# TPS7A4701_and_3301.net
KiCad netlist of a schematic drawn in Altium Designer
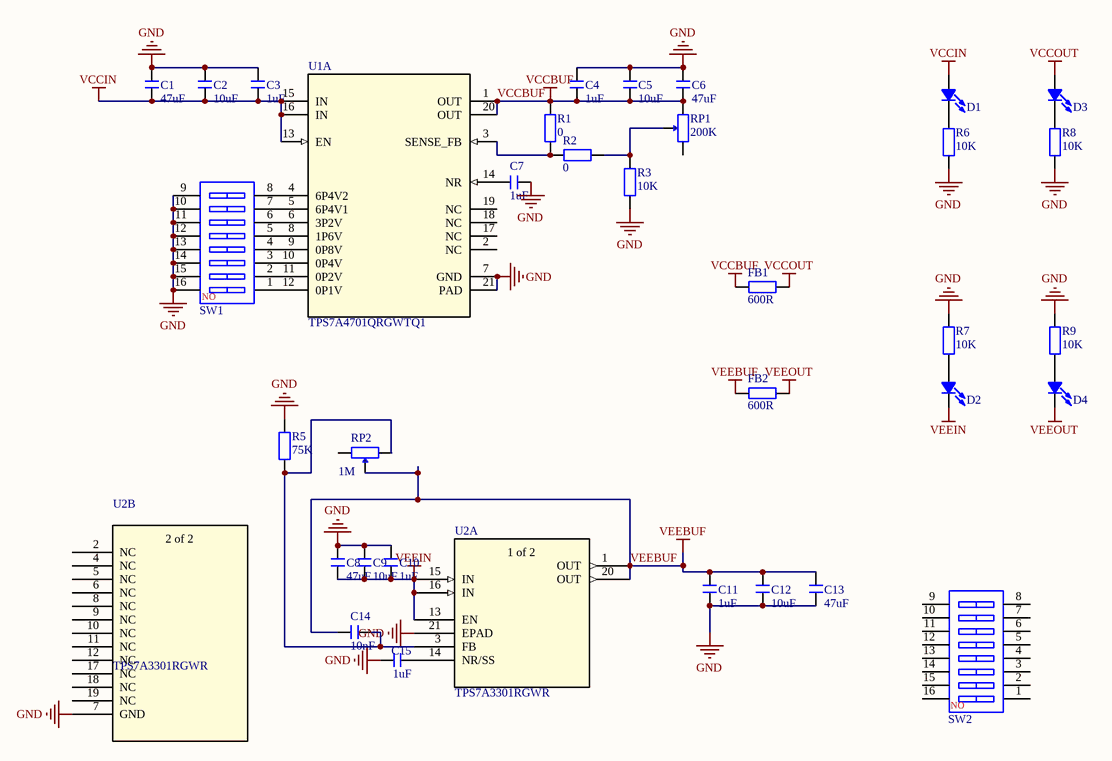
[diagram p0: TPS7A4701 and 3301.SchDoc]

(export (version "E")
  (design (tool "Eeschema 10.0.6"))
  (components
    (comp (ref "C1")
      (value "47uF")
      (footprint "C 0603_L")
      (description "无极性贴片电容")
      (fields (field (name "版权归属") "源创客"))
      (libsource (lib "IL") (part "C"))
    )
    (comp (ref "C2")
      (value "10uF")
      (footprint "C 0603_L")
      (description "无极性贴片电容")
      (fields (field (name "版权归属") "源创客"))
      (libsource (lib "IL") (part "C"))
    )
    (comp (ref "C3")
      (value "1uF")
      (footprint "C 0603_L")
      (description "无极性贴片电容")
      (fields (field (name "版权归属") "源创客"))
      (libsource (lib "IL") (part "C"))
    )
    (comp (ref "C4")
      (value "1uF")
      (footprint "C 0603_L")
      (description "无极性贴片电容")
      (fields (field (name "版权归属") "源创客"))
      (libsource (lib "IL") (part "C"))
    )
    (comp (ref "C5")
      (value "10uF")
      (footprint "C 0603_L")
      (description "无极性贴片电容")
      (fields (field (name "版权归属") "源创客"))
      (libsource (lib "IL") (part "C"))
    )
    (comp (ref "C6")
      (value "47uF")
      (footprint "C 0603_L")
      (description "无极性贴片电容")
      (fields (field (name "版权归属") "源创客"))
      (libsource (lib "IL") (part "C"))
    )
    (comp (ref "C7")
      (value "1uF")
      (footprint "C 0603_L")
      (description "无极性贴片电容")
      (fields (field (name "版权归属") "源创客"))
      (libsource (lib "IL") (part "C"))
    )
    (comp (ref "C8")
      (value "47uF")
      (footprint "C 0603_L")
      (description "无极性贴片电容")
      (fields (field (name "版权归属") "源创客"))
      (libsource (lib "IL") (part "C"))
    )
    (comp (ref "C9")
      (value "10uF")
      (footprint "C 0603_L")
      (description "无极性贴片电容")
      (fields (field (name "版权归属") "源创客"))
      (libsource (lib "IL") (part "C"))
    )
    (comp (ref "C10")
      (value "1uF")
      (footprint "C 0603_L")
      (description "无极性贴片电容")
      (fields (field (name "版权归属") "源创客"))
      (libsource (lib "IL") (part "C"))
    )
    (comp (ref "C11")
      (value "1uF")
      (footprint "C 0603_L")
      (description "无极性贴片电容")
      (fields (field (name "版权归属") "源创客"))
      (libsource (lib "IL") (part "C"))
    )
    (comp (ref "C12")
      (value "10uF")
      (footprint "C 0603_L")
      (description "无极性贴片电容")
      (fields (field (name "版权归属") "源创客"))
      (libsource (lib "IL") (part "C"))
    )
    (comp (ref "C13")
      (value "47uF")
      (footprint "C 0603_L")
      (description "无极性贴片电容")
      (fields (field (name "版权归属") "源创客"))
      (libsource (lib "IL") (part "C"))
    )
    (comp (ref "C14")
      (value "10nF")
      (footprint "C 0603_L")
      (description "无极性贴片电容")
      (fields (field (name "版权归属") "源创客"))
      (libsource (lib "IL") (part "C"))
    )
    (comp (ref "C15")
      (value "1uF")
      (footprint "C 0603_L")
      (description "无极性贴片电容")
      (fields (field (name "版权归属") "源创客"))
      (libsource (lib "IL") (part "C"))
    )
    (comp (ref "D1")
      (value "LED")
      (footprint "Led-0805_L")
      (description "发光二极管")
      (libsource (lib "Library") (part "LED"))
    )
    (comp (ref "D2")
      (value "LED")
      (footprint "Led-0805_L")
      (description "发光二极管")
      (libsource (lib "Library") (part "LED"))
    )
    (comp (ref "D3")
      (value "LED")
      (footprint "Led-0805_L")
      (description "发光二极管")
      (libsource (lib "Library") (part "LED"))
    )
    (comp (ref "D4")
      (value "LED")
      (footprint "Led-0805_L")
      (description "发光二极管")
      (libsource (lib "Library") (part "LED"))
    )
    (comp (ref "FB1") (value "600R") (footprint "FB-0805") (libsource (lib "Library") (part "FB")))
    (comp (ref "FB2") (value "600R") (footprint "FB-0805") (libsource (lib "Library") (part "FB")))
    (comp (ref "R1")
      (value "0")
      (footprint "R 0603_L")
      (description "贴片电阻")
      (fields (field (name "版权归属") "源创客"))
      (libsource (lib "IL") (part "R"))
    )
    (comp (ref "R2")
      (value "0")
      (footprint "R 0603_L")
      (description "贴片电阻")
      (fields (field (name "版权归属") "源创客"))
      (libsource (lib "IL") (part "R"))
    )
    (comp (ref "R3")
      (value "10K")
      (footprint "R 0603_L")
      (description "贴片电阻")
      (fields (field (name "版权归属") "源创客"))
      (libsource (lib "IL") (part "R"))
    )
    (comp (ref "R5")
      (value "75K")
      (footprint "R 0603_L")
      (description "贴片电阻")
      (fields (field (name "版权归属") "源创客"))
      (libsource (lib "IL") (part "R"))
    )
    (comp (ref "R6")
      (value "10K")
      (footprint "R 0603_L")
      (description "贴片电阻")
      (fields (field (name "版权归属") "源创客"))
      (libsource (lib "IL") (part "R"))
    )
    (comp (ref "R7")
      (value "10K")
      (footprint "R 0603_L")
      (description "贴片电阻")
      (fields (field (name "版权归属") "源创客"))
      (libsource (lib "IL") (part "R"))
    )
    (comp (ref "R8")
      (value "10K")
      (footprint "R 0603_L")
      (description "贴片电阻")
      (fields (field (name "版权归属") "源创客"))
      (libsource (lib "IL") (part "R"))
    )
    (comp (ref "R9")
      (value "10K")
      (footprint "R 0603_L")
      (description "贴片电阻")
      (fields (field (name "版权归属") "源创客"))
      (libsource (lib "IL") (part "R"))
    )
    (comp (ref "RP1")
      (value "200K")
      (footprint "3296W")
      (description "插件单联电位器")
      (fields (field (name "版权归属") "源创客"))
      (libsource (lib "IL") (part "RP-ID"))
    )
    (comp (ref "RP2")
      (value "1M")
      (footprint "3296W")
      (description "插件单联电位器")
      (fields (field (name "版权归属") "源创客"))
      (libsource (lib "IL") (part "RP-ID"))
    )
    (comp (ref "SW1")
      (value "CSW-8P")
      (footprint "CSW DIP-8P")
      (description "8路编码开关")
      (fields (field (name "版权归属") "源创客"))
      (libsource (lib "IL") (part "CSW-8P"))
    )
    (comp (ref "SW2")
      (value "CSW-8P")
      (footprint "CSW DIP-8P")
      (description "8路编码开关")
      (fields (field (name "版权归属") "源创客"))
      (libsource (lib "IL") (part "CSW-8P"))
    )
    (comp (ref "U1A")
      (value "TPS7A4701QRGWTQ1")
      (footprint "other:RGW0020A")
      (description "No Description Available")
      (fields
        (field (name "MANUFACTURER") "Texas Instruments")
        (field (name "PARTNUMBER") "TPS7A4701QRGWRQ1")
        (field (name "COPYRIGHT") "Copyright (C) 2021 Accelerated Designs. All rights reserved")
      )
      (libsource (lib "IL") (part "TPS7A4701QRGWTQ1"))
    )
    (comp (ref "U2")
      (value "TPS7A3301RGWR")
      (footprint "other:RGW0020A")
      (description "Vin -3V to -36V, -1A, Ultra-Low Noise, High PSRR, Low-Dropout Linear Regulator")
      (fields
        (field (name "MANUFACTURER") "Texas Instruments")
        (field (name "GENERIC_PART_NUMBER") "TPS7A3301")
        (field (name "COPYRIGHT") "Copyright (C) 2021 Accelerated Designs. All rights reserved")
      )
      (libsource (lib "IL") (part "TPS7A3301RGWR_1"))
    )
  )
  (nets
    (net (code "1") (name "GND") (class "Default")
      (node (ref "C1") (pin "2") (pinfunction "2_2") (pintype "passive"))
      (node (ref "C10") (pin "2") (pinfunction "2_2") (pintype "passive"))
      (node (ref "C11") (pin "1") (pinfunction "1_1") (pintype "passive"))
      (node (ref "C12") (pin "1") (pinfunction "1_1") (pintype "passive"))
      (node (ref "C13") (pin "1") (pinfunction "1_1") (pintype "passive"))
      (node (ref "C15") (pin "2") (pinfunction "2_2") (pintype "passive"))
      (node (ref "C2") (pin "2") (pinfunction "2_2") (pintype "passive"))
      (node (ref "C3") (pin "2") (pinfunction "2_2") (pintype "passive"))
      (node (ref "C4") (pin "2") (pinfunction "2_2") (pintype "passive"))
      (node (ref "C5") (pin "2") (pinfunction "2_2") (pintype "passive"))
      (node (ref "C6") (pin "2") (pinfunction "2_2") (pintype "passive"))
      (node (ref "C7") (pin "2") (pinfunction "2_2") (pintype "passive"))
      (node (ref "C8") (pin "2") (pinfunction "2_2") (pintype "passive"))
      (node (ref "C9") (pin "2") (pinfunction "2_2") (pintype "passive"))
      (node (ref "R3") (pin "1") (pinfunction "1_1") (pintype "passive"))
      (node (ref "R5") (pin "1") (pinfunction "1_1") (pintype "passive"))
      (node (ref "R6") (pin "1") (pinfunction "1_1") (pintype "passive"))
      (node (ref "R7") (pin "2") (pinfunction "2_2") (pintype "passive"))
      (node (ref "R8") (pin "1") (pinfunction "1_1") (pintype "passive"))
      (node (ref "R9") (pin "2") (pinfunction "2_2") (pintype "passive"))
      (node (ref "SW1") (pin "10") (pinfunction "10_10") (pintype "passive"))
      (node (ref "SW1") (pin "11") (pinfunction "11_11") (pintype "passive"))
      (node (ref "SW1") (pin "12") (pinfunction "12_12") (pintype "passive"))
      (node (ref "SW1") (pin "13") (pinfunction "13_13") (pintype "passive"))
      (node (ref "SW1") (pin "14") (pinfunction "14_14") (pintype "passive"))
      (node (ref "SW1") (pin "15") (pinfunction "15_15") (pintype "passive"))
      (node (ref "SW1") (pin "16") (pinfunction "16_16") (pintype "passive"))
      (node (ref "SW1") (pin "9") (pinfunction "9_9") (pintype "passive"))
      (node (ref "U1A") (pin "21") (pinfunction "PAD_21") (pintype "passive"))
      (node (ref "U1A") (pin "7") (pinfunction "GND_7") (pintype "power_in"))
      (node (ref "U2") (pin "21") (pinfunction "EPAD_21") (pintype "passive"))
      (node (ref "U2") (pin "7") (pinfunction "GND_7") (pintype "power_in"))
    )
    (net (code "2") (name "Net-(D1-Pad2)") (class "Default")
      (node (ref "D1") (pin "2") (pinfunction "2_2") (pintype "passive"))
      (node (ref "R6") (pin "2") (pinfunction "2_2") (pintype "passive"))
    )
    (net (code "3") (name "Net-(D2-Pad1)") (class "Default")
      (node (ref "D2") (pin "1") (pinfunction "1_1") (pintype "passive"))
      (node (ref "R7") (pin "1") (pinfunction "1_1") (pintype "passive"))
    )
    (net (code "4") (name "Net-(D3-Pad2)") (class "Default")
      (node (ref "D3") (pin "2") (pinfunction "2_2") (pintype "passive"))
      (node (ref "R8") (pin "2") (pinfunction "2_2") (pintype "passive"))
    )
    (net (code "5") (name "Net-(D4-Pad1)") (class "Default")
      (node (ref "D4") (pin "1") (pinfunction "1_1") (pintype "passive"))
      (node (ref "R9") (pin "1") (pinfunction "1_1") (pintype "passive"))
    )
    (net (code "6") (name "Net-(R2-Pad1)") (class "Default")
      (node (ref "R2") (pin "1") (pinfunction "1_1") (pintype "passive"))
      (node (ref "R3") (pin "2") (pinfunction "2_2") (pintype "passive"))
      (node (ref "RP1") (pin "2") (pinfunction "2_2") (pintype "passive"))
    )
    (net (code "7") (name "Net-(U1A-0P1V)") (class "Default")
      (node (ref "SW1") (pin "1") (pinfunction "1_1") (pintype "passive"))
      (node (ref "U1A") (pin "12") (pinfunction "0P1V_12") (pintype "passive"))
    )
    (net (code "8") (name "Net-(U1A-0P2V)") (class "Default")
      (node (ref "SW1") (pin "2") (pinfunction "2_2") (pintype "passive"))
      (node (ref "U1A") (pin "11") (pinfunction "0P2V_11") (pintype "passive"))
    )
    (net (code "9") (name "Net-(U1A-0P4V)") (class "Default")
      (node (ref "SW1") (pin "3") (pinfunction "3_3") (pintype "passive"))
      (node (ref "U1A") (pin "10") (pinfunction "0P4V_10") (pintype "passive"))
    )
    (net (code "10") (name "Net-(U1A-0P8V)") (class "Default")
      (node (ref "SW1") (pin "4") (pinfunction "4_4") (pintype "passive"))
      (node (ref "U1A") (pin "9") (pinfunction "0P8V_9") (pintype "passive"))
    )
    (net (code "11") (name "Net-(U1A-1P6V)") (class "Default")
      (node (ref "SW1") (pin "5") (pinfunction "5_5") (pintype "passive"))
      (node (ref "U1A") (pin "8") (pinfunction "1P6V_8") (pintype "passive"))
    )
    (net (code "12") (name "Net-(U1A-3P2V)") (class "Default")
      (node (ref "SW1") (pin "6") (pinfunction "6_6") (pintype "passive"))
      (node (ref "U1A") (pin "6") (pinfunction "3P2V_6") (pintype "passive"))
    )
    (net (code "13") (name "Net-(U1A-6P4V1)") (class "Default")
      (node (ref "SW1") (pin "7") (pinfunction "7_7") (pintype "passive"))
      (node (ref "U1A") (pin "5") (pinfunction "6P4V1_5") (pintype "passive"))
    )
    (net (code "14") (name "Net-(U1A-6P4V2)") (class "Default")
      (node (ref "SW1") (pin "8") (pinfunction "8_8") (pintype "passive"))
      (node (ref "U1A") (pin "4") (pinfunction "6P4V2_4") (pintype "passive"))
    )
    (net (code "15") (name "Net-(U1A-NR)") (class "Default")
      (node (ref "C7") (pin "1") (pinfunction "1_1") (pintype "passive"))
      (node (ref "U1A") (pin "14") (pinfunction "NR_14") (pintype "input"))
    )
    (net (code "16") (name "Net-(U1A-SENSE_FB)") (class "Default")
      (node (ref "R1") (pin "1") (pinfunction "1_1") (pintype "passive"))
      (node (ref "R2") (pin "2") (pinfunction "2_2") (pintype "passive"))
      (node (ref "U1A") (pin "3") (pinfunction "SENSE_FB_3") (pintype "input"))
    )
    (net (code "17") (name "Net-(U2A-FB)") (class "Default")
      (node (ref "C14") (pin "1") (pinfunction "1_1") (pintype "passive"))
      (node (ref "R5") (pin "2") (pinfunction "2_2") (pintype "passive"))
      (node (ref "RP2") (pin "3") (pinfunction "3_3") (pintype "passive"))
      (node (ref "U2") (pin "3") (pinfunction "FB_3") (pintype "passive"))
    )
    (net (code "18") (name "Net-(U2A-NR{slash}SS)") (class "Default")
      (node (ref "C15") (pin "1") (pinfunction "1_1") (pintype "passive"))
      (node (ref "U2") (pin "14") (pinfunction "NR/SS_14") (pintype "passive"))
    )
    (net (code "19") (name "VCCBUF") (class "Default")
      (node (ref "C4") (pin "1") (pinfunction "1_1") (pintype "passive"))
      (node (ref "C5") (pin "1") (pinfunction "1_1") (pintype "passive"))
      (node (ref "C6") (pin "1") (pinfunction "1_1") (pintype "passive"))
      (node (ref "FB1") (pin "1") (pinfunction "1_1") (pintype "passive"))
      (node (ref "R1") (pin "2") (pinfunction "2_2") (pintype "passive"))
      (node (ref "RP1") (pin "1") (pinfunction "1_1") (pintype "passive"))
      (node (ref "U1A") (pin "1") (pinfunction "OUT_1") (pintype "power_in"))
      (node (ref "U1A") (pin "20") (pinfunction "OUT_20") (pintype "power_in"))
    )
    (net (code "20") (name "VCCIN") (class "Default")
      (node (ref "C1") (pin "1") (pinfunction "1_1") (pintype "passive"))
      (node (ref "C2") (pin "1") (pinfunction "1_1") (pintype "passive"))
      (node (ref "C3") (pin "1") (pinfunction "1_1") (pintype "passive"))
      (node (ref "D1") (pin "1") (pinfunction "1_1") (pintype "passive"))
      (node (ref "U1A") (pin "13") (pinfunction "EN_13") (pintype "input"))
      (node (ref "U1A") (pin "15") (pinfunction "IN_15") (pintype "power_in"))
      (node (ref "U1A") (pin "16") (pinfunction "IN_16") (pintype "power_in"))
    )
    (net (code "21") (name "VCCOUT") (class "Default")
      (node (ref "D3") (pin "1") (pinfunction "1_1") (pintype "passive"))
      (node (ref "FB1") (pin "2") (pinfunction "2_2") (pintype "passive"))
    )
    (net (code "22") (name "VEEBUF") (class "Default")
      (node (ref "C11") (pin "2") (pinfunction "2_2") (pintype "passive"))
      (node (ref "C12") (pin "2") (pinfunction "2_2") (pintype "passive"))
      (node (ref "C13") (pin "2") (pinfunction "2_2") (pintype "passive"))
      (node (ref "C14") (pin "2") (pinfunction "2_2") (pintype "passive"))
      (node (ref "FB2") (pin "1") (pinfunction "1_1") (pintype "passive"))
      (node (ref "RP2") (pin "2") (pinfunction "2_2") (pintype "passive"))
      (node (ref "U2") (pin "1") (pinfunction "OUT_1") (pintype "output"))
      (node (ref "U2") (pin "20") (pinfunction "OUT_20") (pintype "output"))
    )
    (net (code "23") (name "VEEIN") (class "Default")
      (node (ref "C10") (pin "1") (pinfunction "1_1") (pintype "passive"))
      (node (ref "C8") (pin "1") (pinfunction "1_1") (pintype "passive"))
      (node (ref "C9") (pin "1") (pinfunction "1_1") (pintype "passive"))
      (node (ref "D2") (pin "2") (pinfunction "2_2") (pintype "passive"))
      (node (ref "U2") (pin "13") (pinfunction "EN_13") (pintype "passive"))
      (node (ref "U2") (pin "15") (pinfunction "IN_15") (pintype "input"))
      (node (ref "U2") (pin "16") (pinfunction "IN_16") (pintype "input"))
    )
    (net (code "24") (name "VEEOUT") (class "Default")
      (node (ref "D4") (pin "2") (pinfunction "2_2") (pintype "passive"))
      (node (ref "FB2") (pin "2") (pinfunction "2_2") (pintype "passive"))
    )
    (net (code "25") (name "unconnected-(RP1-Pad3)") (class "Default")
      (node (ref "RP1") (pin "3") (pinfunction "3_3") (pintype "passive"))
    )
    (net (code "26") (name "unconnected-(RP2-Pad1)") (class "Default")
      (node (ref "RP2") (pin "1") (pinfunction "1_1") (pintype "passive"))
    )
    (net (code "27") (name "unconnected-(SW2-Pad1)") (class "Default")
      (node (ref "SW2") (pin "1") (pinfunction "1_1") (pintype "passive"))
    )
    (net (code "28") (name "unconnected-(SW2-Pad2)") (class "Default")
      (node (ref "SW2") (pin "2") (pinfunction "2_2") (pintype "passive"))
    )
    (net (code "29") (name "unconnected-(SW2-Pad3)") (class "Default")
      (node (ref "SW2") (pin "3") (pinfunction "3_3") (pintype "passive"))
    )
    (net (code "30") (name "unconnected-(SW2-Pad4)") (class "Default")
      (node (ref "SW2") (pin "4") (pinfunction "4_4") (pintype "passive"))
    )
    (net (code "31") (name "unconnected-(SW2-Pad5)") (class "Default")
      (node (ref "SW2") (pin "5") (pinfunction "5_5") (pintype "passive"))
    )
    (net (code "32") (name "unconnected-(SW2-Pad6)") (class "Default")
      (node (ref "SW2") (pin "6") (pinfunction "6_6") (pintype "passive"))
    )
    (net (code "33") (name "unconnected-(SW2-Pad7)") (class "Default")
      (node (ref "SW2") (pin "7") (pinfunction "7_7") (pintype "passive"))
    )
    (net (code "34") (name "unconnected-(SW2-Pad8)") (class "Default")
      (node (ref "SW2") (pin "8") (pinfunction "8_8") (pintype "passive"))
    )
    (net (code "35") (name "unconnected-(SW2-Pad9)") (class "Default")
      (node (ref "SW2") (pin "9") (pinfunction "9_9") (pintype "passive"))
    )
    (net (code "36") (name "unconnected-(SW2-Pad10)") (class "Default")
      (node (ref "SW2") (pin "10") (pinfunction "10_10") (pintype "passive"))
    )
    (net (code "37") (name "unconnected-(SW2-Pad11)") (class "Default")
      (node (ref "SW2") (pin "11") (pinfunction "11_11") (pintype "passive"))
    )
    (net (code "38") (name "unconnected-(SW2-Pad12)") (class "Default")
      (node (ref "SW2") (pin "12") (pinfunction "12_12") (pintype "passive"))
    )
    (net (code "39") (name "unconnected-(SW2-Pad13)") (class "Default")
      (node (ref "SW2") (pin "13") (pinfunction "13_13") (pintype "passive"))
    )
    (net (code "40") (name "unconnected-(SW2-Pad14)") (class "Default")
      (node (ref "SW2") (pin "14") (pinfunction "14_14") (pintype "passive"))
    )
    (net (code "41") (name "unconnected-(SW2-Pad15)") (class "Default")
      (node (ref "SW2") (pin "15") (pinfunction "15_15") (pintype "passive"))
    )
    (net (code "42") (name "unconnected-(SW2-Pad16)") (class "Default")
      (node (ref "SW2") (pin "16") (pinfunction "16_16") (pintype "passive"))
    )
    (net (code "43") (name "unconnected-(U1A-NC-Pad2)") (class "Default")
      (node (ref "U1A") (pin "2") (pinfunction "NC_2") (pintype "passive"))
    )
    (net (code "44") (name "unconnected-(U1A-NC-Pad17)") (class "Default")
      (node (ref "U1A") (pin "17") (pinfunction "NC_17") (pintype "passive"))
    )
    (net (code "45") (name "unconnected-(U1A-NC-Pad18)") (class "Default")
      (node (ref "U1A") (pin "18") (pinfunction "NC_18") (pintype "passive"))
    )
    (net (code "46") (name "unconnected-(U1A-NC-Pad19)") (class "Default")
      (node (ref "U1A") (pin "19") (pinfunction "NC_19") (pintype "passive"))
    )
    (net (code "47") (name "unconnected-(U2B-NC-Pad2)") (class "Default")
      (node (ref "U2") (pin "2") (pinfunction "NC_2") (pintype "passive"))
    )
    (net (code "48") (name "unconnected-(U2B-NC-Pad4)") (class "Default")
      (node (ref "U2") (pin "4") (pinfunction "NC_4") (pintype "passive"))
    )
    (net (code "49") (name "unconnected-(U2B-NC-Pad5)") (class "Default")
      (node (ref "U2") (pin "5") (pinfunction "NC_5") (pintype "passive"))
    )
    (net (code "50") (name "unconnected-(U2B-NC-Pad6)") (class "Default")
      (node (ref "U2") (pin "6") (pinfunction "NC_6") (pintype "passive"))
    )
    (net (code "51") (name "unconnected-(U2B-NC-Pad8)") (class "Default")
      (node (ref "U2") (pin "8") (pinfunction "NC_8") (pintype "passive"))
    )
    (net (code "52") (name "unconnected-(U2B-NC-Pad9)") (class "Default")
      (node (ref "U2") (pin "9") (pinfunction "NC_9") (pintype "passive"))
    )
    (net (code "53") (name "unconnected-(U2B-NC-Pad10)") (class "Default")
      (node (ref "U2") (pin "10") (pinfunction "NC_10") (pintype "passive"))
    )
    (net (code "54") (name "unconnected-(U2B-NC-Pad11)") (class "Default")
      (node (ref "U2") (pin "11") (pinfunction "NC_11") (pintype "passive"))
    )
    (net (code "55") (name "unconnected-(U2B-NC-Pad12)") (class "Default")
      (node (ref "U2") (pin "12") (pinfunction "NC_12") (pintype "passive"))
    )
    (net (code "56") (name "unconnected-(U2B-NC-Pad17)") (class "Default")
      (node (ref "U2") (pin "17") (pinfunction "NC_17") (pintype "passive"))
    )
    (net (code "57") (name "unconnected-(U2B-NC-Pad18)") (class "Default")
      (node (ref "U2") (pin "18") (pinfunction "NC_18") (pintype "passive"))
    )
    (net (code "58") (name "unconnected-(U2B-NC-Pad19)") (class "Default")
      (node (ref "U2") (pin "19") (pinfunction "NC_19") (pintype "passive"))
    )
  )
)
